# Nusbio_2_-_IC2_Extension.net
KiCad netlist of a schematic drawn in EAGLE
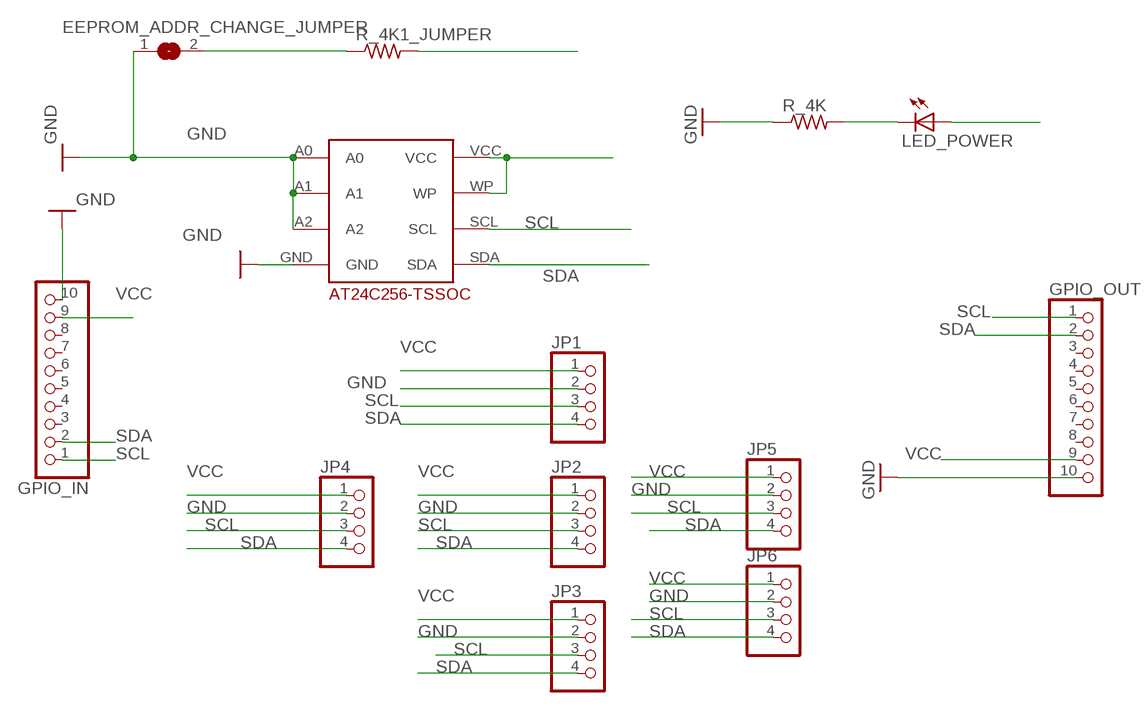
[diagram p0: schematic, sheet 1]

(export (version "E")
  (design (tool "Eeschema 10.0.6"))
  (components
    (comp (ref "EEPROM_ADDR_CHANGE_JUMPER")
      (value "SOLDERJUMPERREFLOW")
      (footprint "eagle-import:SOLDERJUMPER_REFLOW")
      (libsource (lib "eagle-import") (part "SOLDERJUMPERREFLOW"))
    )
    (comp (ref "EEPROM_AT24C256")
      (value "DECADE-AT24C256-10TI-2.7")
      (footprint "eagle-import:DECADE-AT24CXX")
      (libsource (lib "eagle-import") (part "DECADE-AT24C256-10TI-2.7"))
    )
    (comp (ref "GPIO_IN")
      (value "PINHD-1X10")
      (footprint "eagle-import:1X10-BIG")
      (libsource (lib "eagle-import") (part "PINHD-1X10"))
    )
    (comp (ref "GPIO_OUT")
      (value "PINHD-1X10")
      (footprint "eagle-import:1X10-BIG")
      (libsource (lib "eagle-import") (part "PINHD-1X10"))
    )
    (comp (ref "JP1")
      (value "PINHD-1X4")
      (footprint "eagle-import:1X04")
      (libsource (lib "eagle-import") (part "PINHD-1X4"))
    )
    (comp (ref "JP2")
      (value "PINHD-1X4")
      (footprint "eagle-import:1X04")
      (libsource (lib "eagle-import") (part "PINHD-1X4"))
    )
    (comp (ref "JP3")
      (value "PINHD-1X4")
      (footprint "eagle-import:1X04")
      (libsource (lib "eagle-import") (part "PINHD-1X4"))
    )
    (comp (ref "JP4")
      (value "PINHD-1X4")
      (footprint "eagle-import:1X04")
      (libsource (lib "eagle-import") (part "PINHD-1X4"))
    )
    (comp (ref "JP5")
      (value "PINHD-1X4")
      (footprint "eagle-import:1X04")
      (libsource (lib "eagle-import") (part "PINHD-1X4"))
    )
    (comp (ref "JP6")
      (value "PINHD-1X4")
      (footprint "eagle-import:1X04")
      (libsource (lib "eagle-import") (part "PINHD-1X4"))
    )
    (comp (ref "LED_POWER")
      (value "LEDSMT1206")
      (footprint "eagle-import:1206")
      (libsource (lib "eagle-import") (part "LEDSMT1206"))
    )
    (comp (ref "R_4K")
      (value "R-US_R1206")
      (footprint "eagle-import:R1206")
      (libsource (lib "eagle-import") (part "R-US_R1206"))
    )
    (comp (ref "R_4K1_JUMPER")
      (value "R-US_R1206")
      (footprint "eagle-import:R1206")
      (libsource (lib "eagle-import") (part "R-US_R1206"))
    )
  )
  (nets
    (net (code "1") (name "/SCL") (class "Default")
      (node (ref "EEPROM_AT24C256") (pin "SCL") (pinfunction "SCL_SCL") (pintype "bidirectional"))
      (node (ref "GPIO_IN") (pin "1") (pinfunction "1_1") (pintype "passive"))
      (node (ref "GPIO_OUT") (pin "1") (pinfunction "1_1") (pintype "passive"))
      (node (ref "JP1") (pin "3") (pinfunction "3_3") (pintype "passive"))
      (node (ref "JP2") (pin "3") (pinfunction "3_3") (pintype "passive"))
      (node (ref "JP3") (pin "3") (pinfunction "3_3") (pintype "passive"))
      (node (ref "JP4") (pin "3") (pinfunction "3_3") (pintype "passive"))
      (node (ref "JP5") (pin "3") (pinfunction "3_3") (pintype "passive"))
      (node (ref "JP6") (pin "3") (pinfunction "3_3") (pintype "passive"))
    )
    (net (code "2") (name "/SDA") (class "Default")
      (node (ref "EEPROM_AT24C256") (pin "SDA") (pinfunction "SDA_SDA") (pintype "bidirectional"))
      (node (ref "GPIO_IN") (pin "2") (pinfunction "2_2") (pintype "passive"))
      (node (ref "GPIO_OUT") (pin "2") (pinfunction "2_2") (pintype "passive"))
      (node (ref "JP1") (pin "4") (pinfunction "4_4") (pintype "passive"))
      (node (ref "JP2") (pin "4") (pinfunction "4_4") (pintype "passive"))
      (node (ref "JP3") (pin "4") (pinfunction "4_4") (pintype "passive"))
      (node (ref "JP4") (pin "4") (pinfunction "4_4") (pintype "passive"))
      (node (ref "JP5") (pin "4") (pinfunction "4_4") (pintype "passive"))
      (node (ref "JP6") (pin "4") (pinfunction "4_4") (pintype "passive"))
    )
    (net (code "3") (name "/VCC") (class "Default")
      (node (ref "GPIO_IN") (pin "9") (pinfunction "9_9") (pintype "passive"))
      (node (ref "GPIO_OUT") (pin "9") (pinfunction "9_9") (pintype "passive"))
      (node (ref "JP1") (pin "1") (pinfunction "1_1") (pintype "passive"))
      (node (ref "JP2") (pin "1") (pinfunction "1_1") (pintype "passive"))
      (node (ref "JP3") (pin "1") (pinfunction "1_1") (pintype "passive"))
      (node (ref "JP4") (pin "1") (pinfunction "1_1") (pintype "passive"))
      (node (ref "JP5") (pin "1") (pinfunction "1_1") (pintype "passive"))
      (node (ref "JP6") (pin "1") (pinfunction "1_1") (pintype "passive"))
      (node (ref "LED_POWER") (pin "A") (pinfunction "A_A") (pintype "passive"))
      (node (ref "R_4K1_JUMPER") (pin "2") (pinfunction "2_2") (pintype "passive"))
    )
    (net (code "4") (name "GND") (class "Default")
      (node (ref "EEPROM_ADDR_CHANGE_JUMPER") (pin "1") (pinfunction "1_1") (pintype "passive"))
      (node (ref "EEPROM_AT24C256") (pin "A0") (pinfunction "A0_A0") (pintype "bidirectional"))
      (node (ref "EEPROM_AT24C256") (pin "A1") (pinfunction "A1_A1") (pintype "bidirectional"))
      (node (ref "EEPROM_AT24C256") (pin "A2") (pinfunction "A2_A2") (pintype "bidirectional"))
      (node (ref "EEPROM_AT24C256") (pin "GND") (pinfunction "GND_GND") (pintype "bidirectional"))
      (node (ref "GPIO_IN") (pin "10") (pinfunction "10_10") (pintype "passive"))
      (node (ref "GPIO_OUT") (pin "10") (pinfunction "10_10") (pintype "passive"))
      (node (ref "JP1") (pin "2") (pinfunction "2_2") (pintype "passive"))
      (node (ref "JP2") (pin "2") (pinfunction "2_2") (pintype "passive"))
      (node (ref "JP3") (pin "2") (pinfunction "2_2") (pintype "passive"))
      (node (ref "JP4") (pin "2") (pinfunction "2_2") (pintype "passive"))
      (node (ref "JP5") (pin "2") (pinfunction "2_2") (pintype "passive"))
      (node (ref "JP6") (pin "2") (pinfunction "2_2") (pintype "passive"))
      (node (ref "R_4K") (pin "1") (pinfunction "1_1") (pintype "passive"))
    )
    (net (code "5") (name "Net-(EEPROM_ADDR_CHANGE_JUMPER-Pad2)") (class "Default")
      (node (ref "EEPROM_ADDR_CHANGE_JUMPER") (pin "2") (pinfunction "2_2") (pintype "passive"))
      (node (ref "R_4K1_JUMPER") (pin "1") (pinfunction "1_1") (pintype "passive"))
    )
    (net (code "6") (name "Net-(EEPROM_AT24C256-PadVCC)") (class "Default")
      (node (ref "EEPROM_AT24C256") (pin "VCC") (pinfunction "VCC_VCC") (pintype "bidirectional"))
      (node (ref "EEPROM_AT24C256") (pin "WP") (pinfunction "WP_WP") (pintype "bidirectional"))
    )
    (net (code "7") (name "Net-(LED_POWER-PadC)") (class "Default")
      (node (ref "LED_POWER") (pin "C") (pinfunction "C_C") (pintype "passive"))
      (node (ref "R_4K") (pin "2") (pinfunction "2_2") (pintype "passive"))
    )
    (net (code "8") (name "unconnected-(GPIO_IN-Pad3)") (class "Default")
      (node (ref "GPIO_IN") (pin "3") (pinfunction "3_3") (pintype "passive"))
    )
    (net (code "9") (name "unconnected-(GPIO_IN-Pad4)") (class "Default")
      (node (ref "GPIO_IN") (pin "4") (pinfunction "4_4") (pintype "passive"))
    )
    (net (code "10") (name "unconnected-(GPIO_IN-Pad5)") (class "Default")
      (node (ref "GPIO_IN") (pin "5") (pinfunction "5_5") (pintype "passive"))
    )
    (net (code "11") (name "unconnected-(GPIO_IN-Pad6)") (class "Default")
      (node (ref "GPIO_IN") (pin "6") (pinfunction "6_6") (pintype "passive"))
    )
    (net (code "12") (name "unconnected-(GPIO_IN-Pad7)") (class "Default")
      (node (ref "GPIO_IN") (pin "7") (pinfunction "7_7") (pintype "passive"))
    )
    (net (code "13") (name "unconnected-(GPIO_IN-Pad8)") (class "Default")
      (node (ref "GPIO_IN") (pin "8") (pinfunction "8_8") (pintype "passive"))
    )
    (net (code "14") (name "unconnected-(GPIO_OUT-Pad3)") (class "Default")
      (node (ref "GPIO_OUT") (pin "3") (pinfunction "3_3") (pintype "passive"))
    )
    (net (code "15") (name "unconnected-(GPIO_OUT-Pad4)") (class "Default")
      (node (ref "GPIO_OUT") (pin "4") (pinfunction "4_4") (pintype "passive"))
    )
    (net (code "16") (name "unconnected-(GPIO_OUT-Pad5)") (class "Default")
      (node (ref "GPIO_OUT") (pin "5") (pinfunction "5_5") (pintype "passive"))
    )
    (net (code "17") (name "unconnected-(GPIO_OUT-Pad6)") (class "Default")
      (node (ref "GPIO_OUT") (pin "6") (pinfunction "6_6") (pintype "passive"))
    )
    (net (code "18") (name "unconnected-(GPIO_OUT-Pad7)") (class "Default")
      (node (ref "GPIO_OUT") (pin "7") (pinfunction "7_7") (pintype "passive"))
    )
    (net (code "19") (name "unconnected-(GPIO_OUT-Pad8)") (class "Default")
      (node (ref "GPIO_OUT") (pin "8") (pinfunction "8_8") (pintype "passive"))
    )
  )
)
